# KeyBoard-RP2040_P2.net
KiCad netlist of a schematic drawn in Altium Designer
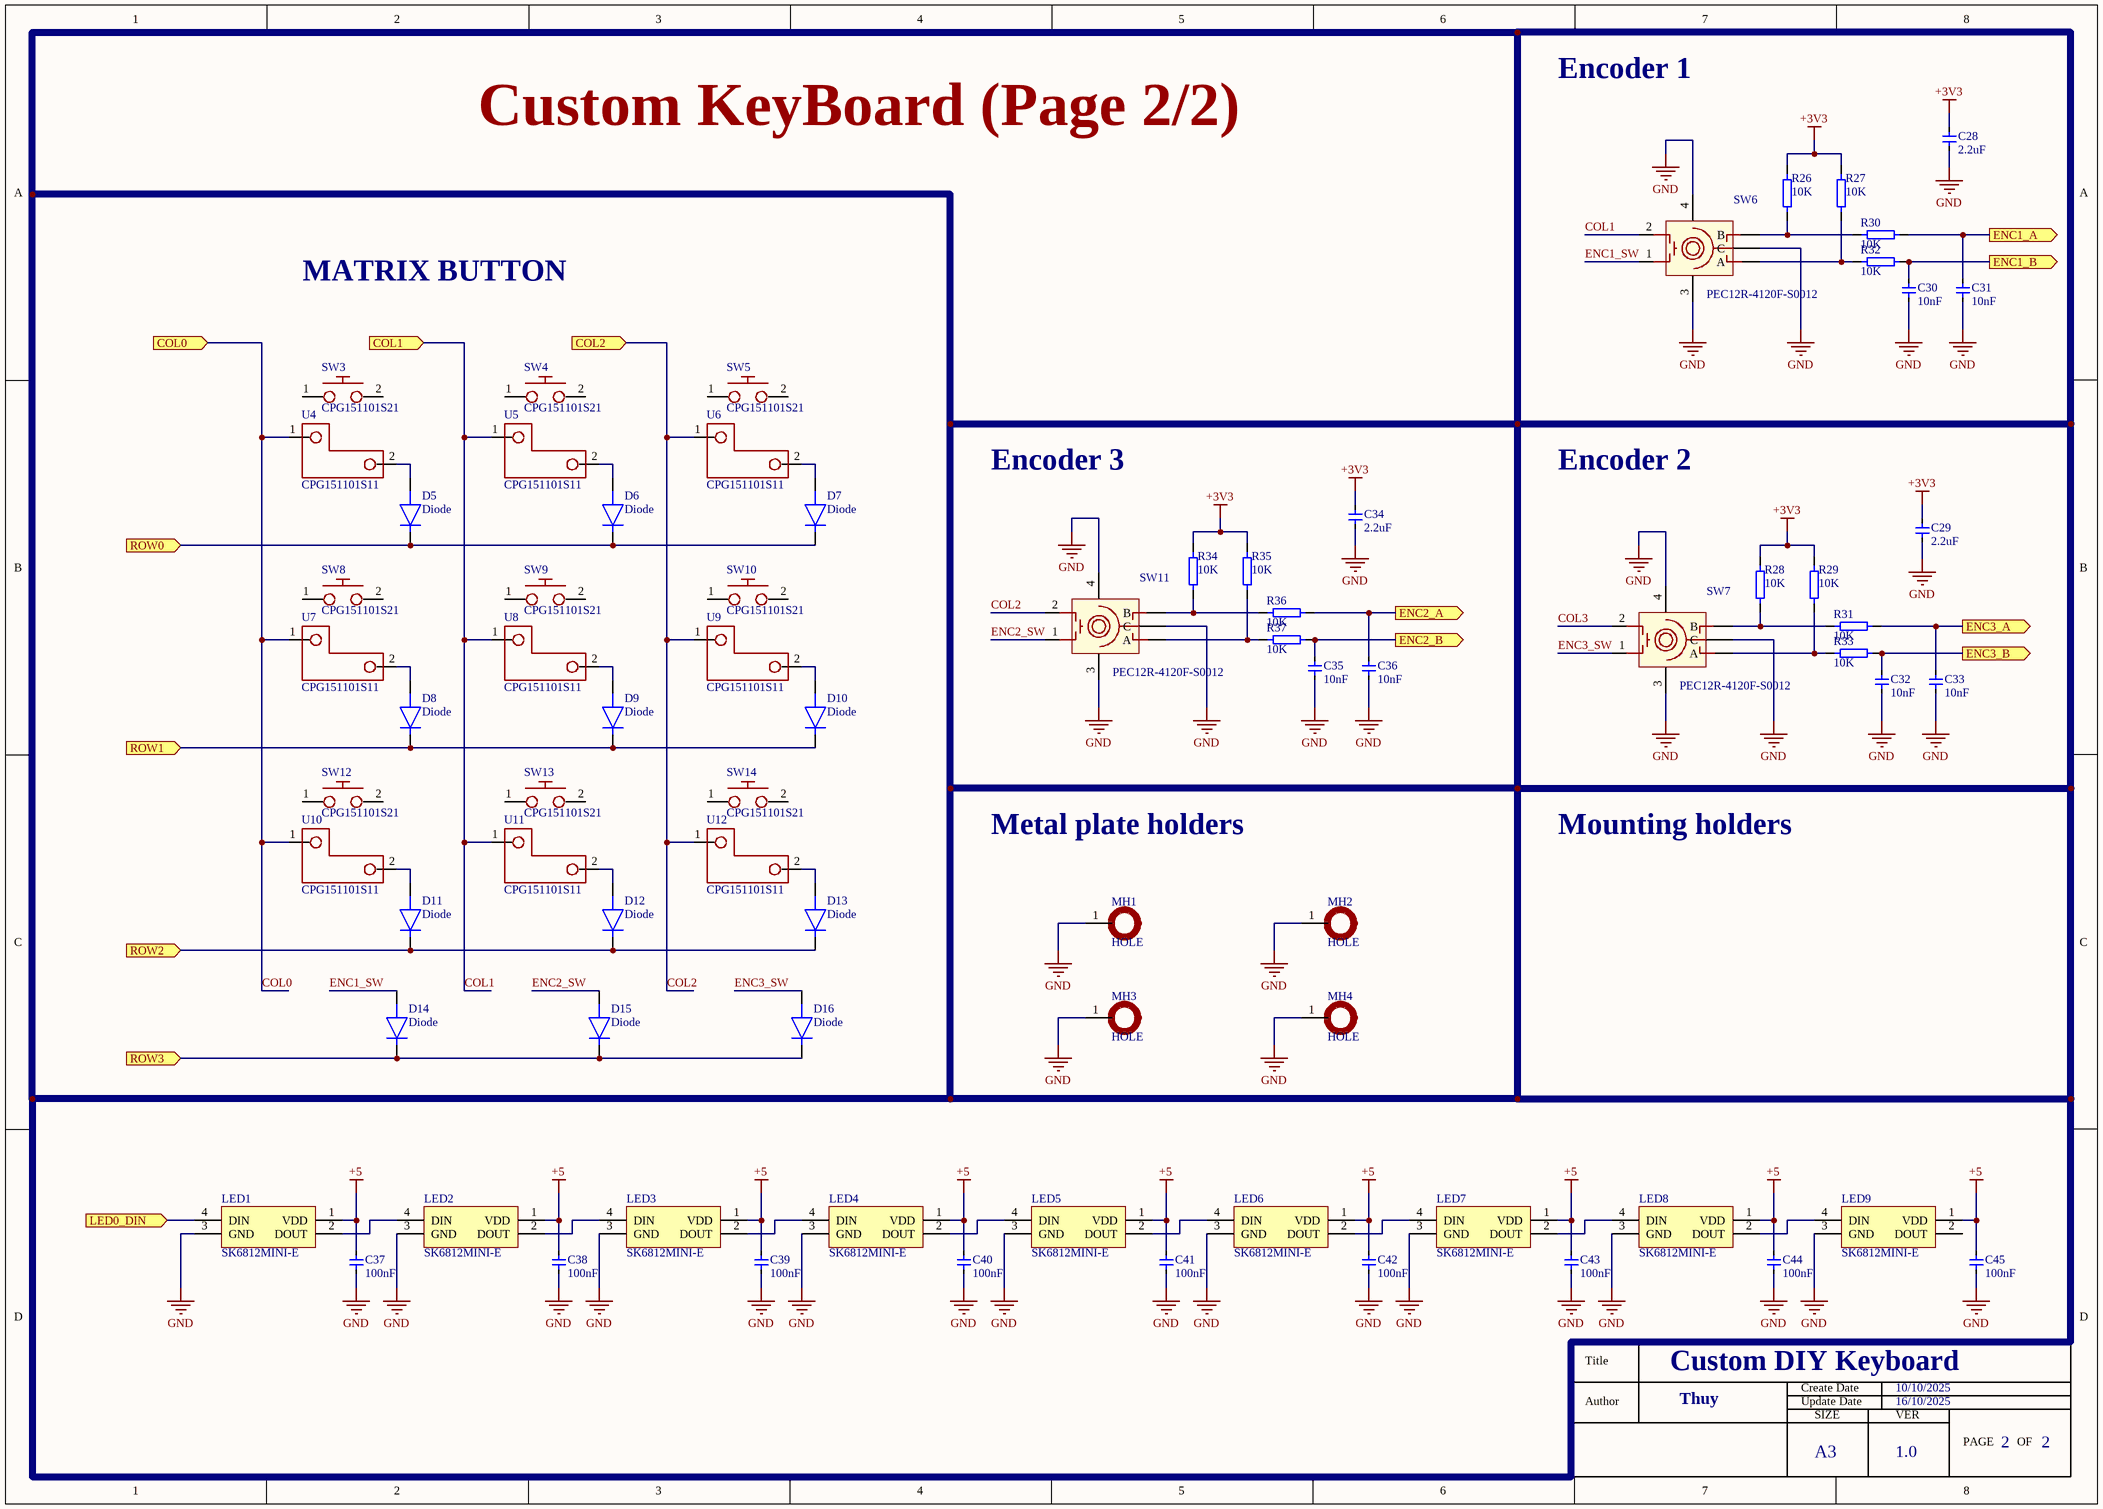
[diagram p0: KeyBoard-RP2040_P2.SchDoc]

(export (version "E")
  (design (tool "Eeschema 10.0.6"))
  (components
    (comp (ref "C28")
      (value "2.2uF")
      (footprint "C 0.79 0.54")
      (description "SMD")
      (libsource (lib "SCHLib") (part "CAP 2.2uF"))
    )
    (comp (ref "C29")
      (value "2.2uF")
      (footprint "C 0.79 0.54")
      (description "SMD")
      (libsource (lib "SCHLib") (part "CAP 2.2uF"))
    )
    (comp (ref "C30")
      (value "10nF")
      (footprint "SMD 0.79 0.54")
      (description "SMD")
      (libsource (lib "SCHLib") (part "CAP 10nF"))
    )
    (comp (ref "C31")
      (value "10nF")
      (footprint "SMD 0.79 0.54")
      (description "SMD")
      (libsource (lib "SCHLib") (part "CAP 10nF"))
    )
    (comp (ref "C32")
      (value "10nF")
      (footprint "SMD 0.79 0.54")
      (description "SMD")
      (libsource (lib "SCHLib") (part "CAP 10nF"))
    )
    (comp (ref "C33")
      (value "10nF")
      (footprint "SMD 0.79 0.54")
      (description "SMD")
      (libsource (lib "SCHLib") (part "CAP 10nF"))
    )
    (comp (ref "C34")
      (value "2.2uF")
      (footprint "C 0.79 0.54")
      (description "SMD")
      (libsource (lib "SCHLib") (part "CAP 2.2uF"))
    )
    (comp (ref "C35")
      (value "10nF")
      (footprint "SMD 0.79 0.54")
      (description "SMD")
      (libsource (lib "SCHLib") (part "CAP 10nF"))
    )
    (comp (ref "C36")
      (value "10nF")
      (footprint "SMD 0.79 0.54")
      (description "SMD")
      (libsource (lib "SCHLib") (part "CAP 10nF"))
    )
    (comp (ref "C37")
      (value "100nF")
      (footprint "C 0.79 0.54")
      (description "SMD")
      (libsource (lib "SCHLib") (part "CAP 100nF"))
    )
    (comp (ref "C38")
      (value "100nF")
      (footprint "C 0.79 0.54")
      (description "SMD")
      (libsource (lib "SCHLib") (part "CAP 100nF"))
    )
    (comp (ref "C39")
      (value "100nF")
      (footprint "C 0.79 0.54")
      (description "SMD")
      (libsource (lib "SCHLib") (part "CAP 100nF"))
    )
    (comp (ref "C40")
      (value "100nF")
      (footprint "C 0.79 0.54")
      (description "SMD")
      (libsource (lib "SCHLib") (part "CAP 100nF"))
    )
    (comp (ref "C41")
      (value "100nF")
      (footprint "C 0.79 0.54")
      (description "SMD")
      (libsource (lib "SCHLib") (part "CAP 100nF"))
    )
    (comp (ref "C42")
      (value "100nF")
      (footprint "C 0.79 0.54")
      (description "SMD")
      (libsource (lib "SCHLib") (part "CAP 100nF"))
    )
    (comp (ref "C43")
      (value "100nF")
      (footprint "C 0.79 0.54")
      (description "SMD")
      (libsource (lib "SCHLib") (part "CAP 100nF"))
    )
    (comp (ref "C44")
      (value "100nF")
      (footprint "C 0.79 0.54")
      (description "SMD")
      (libsource (lib "SCHLib") (part "CAP 100nF"))
    )
    (comp (ref "C45")
      (value "100nF")
      (footprint "C 0.79 0.54")
      (description "SMD")
      (libsource (lib "SCHLib") (part "CAP 100nF"))
    )
    (comp (ref "D5")
      (value "Diode")
      (footprint "Diode")
      (description "SMD")
      (libsource (lib "SCHLib") (part "Diode"))
    )
    (comp (ref "D6")
      (value "Diode")
      (footprint "Diode")
      (description "SMD")
      (libsource (lib "SCHLib") (part "Diode"))
    )
    (comp (ref "D7")
      (value "Diode")
      (footprint "Diode")
      (description "SMD")
      (libsource (lib "SCHLib") (part "Diode"))
    )
    (comp (ref "D8")
      (value "Diode")
      (footprint "Diode")
      (description "SMD")
      (libsource (lib "SCHLib") (part "Diode"))
    )
    (comp (ref "D9")
      (value "Diode")
      (footprint "Diode")
      (description "SMD")
      (libsource (lib "SCHLib") (part "Diode"))
    )
    (comp (ref "D10")
      (value "Diode")
      (footprint "Diode")
      (description "SMD")
      (libsource (lib "SCHLib") (part "Diode"))
    )
    (comp (ref "D11")
      (value "Diode")
      (footprint "Diode")
      (description "SMD")
      (libsource (lib "SCHLib") (part "Diode"))
    )
    (comp (ref "D12")
      (value "Diode")
      (footprint "Diode")
      (description "SMD")
      (libsource (lib "SCHLib") (part "Diode"))
    )
    (comp (ref "D13")
      (value "Diode")
      (footprint "Diode")
      (description "SMD")
      (libsource (lib "SCHLib") (part "Diode"))
    )
    (comp (ref "D14")
      (value "Diode")
      (footprint "Diode")
      (description "SMD")
      (libsource (lib "SCHLib") (part "Diode"))
    )
    (comp (ref "D15")
      (value "Diode")
      (footprint "Diode")
      (description "SMD")
      (libsource (lib "SCHLib") (part "Diode"))
    )
    (comp (ref "D16")
      (value "Diode")
      (footprint "Diode")
      (description "SMD")
      (libsource (lib "SCHLib") (part "Diode"))
    )
    (comp (ref "LED1")
      (value "SK6812MINI-E")
      (footprint "LED-SK6812MINI-E")
      (description "RGB 3.7V~5.5V 0.6mA")
      (libsource (lib "SCHLib") (part "LED-SK6812MINI-E"))
    )
    (comp (ref "LED2")
      (value "SK6812MINI-E")
      (footprint "LED-SK6812MINI-E")
      (description "RGB 3.7V~5.5V 0.6mA")
      (libsource (lib "SCHLib") (part "LED-SK6812MINI-E"))
    )
    (comp (ref "LED3")
      (value "SK6812MINI-E")
      (footprint "LED-SK6812MINI-E")
      (description "RGB 3.7V~5.5V 0.6mA")
      (libsource (lib "SCHLib") (part "LED-SK6812MINI-E"))
    )
    (comp (ref "LED4")
      (value "SK6812MINI-E")
      (footprint "LED-SK6812MINI-E")
      (description "RGB 3.7V~5.5V 0.6mA")
      (libsource (lib "SCHLib") (part "LED-SK6812MINI-E"))
    )
    (comp (ref "LED5")
      (value "SK6812MINI-E")
      (footprint "LED-SK6812MINI-E")
      (description "RGB 3.7V~5.5V 0.6mA")
      (libsource (lib "SCHLib") (part "LED-SK6812MINI-E"))
    )
    (comp (ref "LED6")
      (value "SK6812MINI-E")
      (footprint "LED-SK6812MINI-E")
      (description "RGB 3.7V~5.5V 0.6mA")
      (libsource (lib "SCHLib") (part "LED-SK6812MINI-E"))
    )
    (comp (ref "LED7")
      (value "SK6812MINI-E")
      (footprint "LED-SK6812MINI-E")
      (description "RGB 3.7V~5.5V 0.6mA")
      (libsource (lib "SCHLib") (part "LED-SK6812MINI-E"))
    )
    (comp (ref "LED8")
      (value "SK6812MINI-E")
      (footprint "LED-SK6812MINI-E")
      (description "RGB 3.7V~5.5V 0.6mA")
      (libsource (lib "SCHLib") (part "LED-SK6812MINI-E"))
    )
    (comp (ref "LED9")
      (value "SK6812MINI-E")
      (footprint "LED-SK6812MINI-E")
      (description "RGB 3.7V~5.5V 0.6mA")
      (libsource (lib "SCHLib") (part "LED-SK6812MINI-E"))
    )
    (comp (ref "MH1") (value "HOLE") (footprint "Hole") (libsource (lib "SCHLib") (part "HOLE")))
    (comp (ref "MH2") (value "HOLE") (footprint "Hole") (libsource (lib "SCHLib") (part "HOLE")))
    (comp (ref "MH3") (value "HOLE") (footprint "Hole") (libsource (lib "SCHLib") (part "HOLE")))
    (comp (ref "MH4") (value "HOLE") (footprint "Hole") (libsource (lib "SCHLib") (part "HOLE")))
    (comp (ref "R26")
      (value "10K")
      (footprint "SMD 0.566 0.54")
      (description "SMD")
      (libsource (lib "SCHLib") (part "RES 10K"))
    )
    (comp (ref "R27")
      (value "10K")
      (footprint "SMD 0.566 0.54")
      (description "SMD")
      (libsource (lib "SCHLib") (part "RES 10K"))
    )
    (comp (ref "R28")
      (value "10K")
      (footprint "SMD 0.566 0.54")
      (description "SMD")
      (libsource (lib "SCHLib") (part "RES 10K"))
    )
    (comp (ref "R29")
      (value "10K")
      (footprint "SMD 0.566 0.54")
      (description "SMD")
      (libsource (lib "SCHLib") (part "RES 10K"))
    )
    (comp (ref "R30")
      (value "10K")
      (footprint "SMD 0.566 0.54")
      (description "SMD")
      (libsource (lib "") (part "RES 10K_1"))
    )
    (comp (ref "R31")
      (value "10K")
      (footprint "SMD 0.566 0.54")
      (description "SMD")
      (libsource (lib "") (part "RES 10K_1"))
    )
    (comp (ref "R32")
      (value "10K")
      (footprint "SMD 0.566 0.54")
      (description "SMD")
      (libsource (lib "") (part "RES 10K_1"))
    )
    (comp (ref "R33")
      (value "10K")
      (footprint "SMD 0.566 0.54")
      (description "SMD")
      (libsource (lib "") (part "RES 10K_1"))
    )
    (comp (ref "R34")
      (value "10K")
      (footprint "SMD 0.566 0.54")
      (description "SMD")
      (libsource (lib "SCHLib") (part "RES 10K"))
    )
    (comp (ref "R35")
      (value "10K")
      (footprint "SMD 0.566 0.54")
      (description "SMD")
      (libsource (lib "SCHLib") (part "RES 10K"))
    )
    (comp (ref "R36")
      (value "10K")
      (footprint "SMD 0.566 0.54")
      (description "SMD")
      (libsource (lib "") (part "RES 10K_1"))
    )
    (comp (ref "R37")
      (value "10K")
      (footprint "SMD 0.566 0.54")
      (description "SMD")
      (libsource (lib "") (part "RES 10K_1"))
    )
    (comp (ref "SW3")
      (value "CPG151101S21")
      (footprint "CPG151101S21")
      (libsource (lib "SCHLib") (part "SW-CPG151101S21"))
    )
    (comp (ref "SW4")
      (value "CPG151101S21")
      (footprint "CPG151101S21")
      (libsource (lib "SCHLib") (part "SW-CPG151101S21"))
    )
    (comp (ref "SW5")
      (value "CPG151101S21")
      (footprint "CPG151101S21")
      (libsource (lib "SCHLib") (part "SW-CPG151101S21"))
    )
    (comp (ref "SW6")
      (value "PEC12R-4120F-S0012")
      (footprint "SW-encoder")
      (libsource (lib "SCHLib") (part "Encoder-PEC12R"))
    )
    (comp (ref "SW7")
      (value "PEC12R-4120F-S0012")
      (footprint "SW-encoder")
      (libsource (lib "SCHLib") (part "Encoder-PEC12R"))
    )
    (comp (ref "SW8")
      (value "CPG151101S21")
      (footprint "CPG151101S21")
      (libsource (lib "SCHLib") (part "SW-CPG151101S21"))
    )
    (comp (ref "SW9")
      (value "CPG151101S21")
      (footprint "CPG151101S21")
      (libsource (lib "SCHLib") (part "SW-CPG151101S21"))
    )
    (comp (ref "SW10")
      (value "CPG151101S21")
      (footprint "CPG151101S21")
      (libsource (lib "SCHLib") (part "SW-CPG151101S21"))
    )
    (comp (ref "SW11")
      (value "PEC12R-4120F-S0012")
      (footprint "SW-encoder")
      (libsource (lib "SCHLib") (part "Encoder-PEC12R"))
    )
    (comp (ref "SW12")
      (value "CPG151101S21")
      (footprint "CPG151101S21")
      (libsource (lib "SCHLib") (part "SW-CPG151101S21"))
    )
    (comp (ref "SW13")
      (value "CPG151101S21")
      (footprint "CPG151101S21")
      (libsource (lib "SCHLib") (part "SW-CPG151101S21"))
    )
    (comp (ref "SW14")
      (value "CPG151101S21")
      (footprint "CPG151101S21")
      (libsource (lib "SCHLib") (part "SW-CPG151101S21"))
    )
    (comp (ref "U4")
      (value "CPG151101S11")
      (footprint "CPG151101S11")
      (libsource (lib "SCHLib") (part "SW-CPG151101S11"))
    )
    (comp (ref "U5")
      (value "CPG151101S11")
      (footprint "CPG151101S11")
      (libsource (lib "SCHLib") (part "SW-CPG151101S11"))
    )
    (comp (ref "U6")
      (value "CPG151101S11")
      (footprint "CPG151101S11")
      (libsource (lib "SCHLib") (part "SW-CPG151101S11"))
    )
    (comp (ref "U7")
      (value "CPG151101S11")
      (footprint "CPG151101S11")
      (libsource (lib "SCHLib") (part "SW-CPG151101S11"))
    )
    (comp (ref "U8")
      (value "CPG151101S11")
      (footprint "CPG151101S11")
      (libsource (lib "SCHLib") (part "SW-CPG151101S11"))
    )
    (comp (ref "U9")
      (value "CPG151101S11")
      (footprint "CPG151101S11")
      (libsource (lib "SCHLib") (part "SW-CPG151101S11"))
    )
    (comp (ref "U10")
      (value "CPG151101S11")
      (footprint "CPG151101S11")
      (libsource (lib "SCHLib") (part "SW-CPG151101S11"))
    )
    (comp (ref "U11")
      (value "CPG151101S11")
      (footprint "CPG151101S11")
      (libsource (lib "SCHLib") (part "SW-CPG151101S11"))
    )
    (comp (ref "U12")
      (value "CPG151101S11")
      (footprint "CPG151101S11")
      (libsource (lib "SCHLib") (part "SW-CPG151101S11"))
    )
  )
  (nets
    (net (code "1") (name "+3V3") (class "Default")
      (node (ref "C28") (pin "2") (pinfunction "2_2") (pintype "passive"))
      (node (ref "C29") (pin "2") (pinfunction "2_2") (pintype "passive"))
      (node (ref "C34") (pin "2") (pinfunction "2_2") (pintype "passive"))
      (node (ref "R26") (pin "2") (pinfunction "2_2") (pintype "passive"))
      (node (ref "R27") (pin "2") (pinfunction "2_2") (pintype "passive"))
      (node (ref "R28") (pin "2") (pinfunction "2_2") (pintype "passive"))
      (node (ref "R29") (pin "2") (pinfunction "2_2") (pintype "passive"))
      (node (ref "R34") (pin "2") (pinfunction "2_2") (pintype "passive"))
      (node (ref "R35") (pin "2") (pinfunction "2_2") (pintype "passive"))
    )
    (net (code "2") (name "+5") (class "Default")
      (node (ref "C37") (pin "2") (pinfunction "2_2") (pintype "passive"))
      (node (ref "C38") (pin "2") (pinfunction "2_2") (pintype "passive"))
      (node (ref "C39") (pin "2") (pinfunction "2_2") (pintype "passive"))
      (node (ref "C40") (pin "2") (pinfunction "2_2") (pintype "passive"))
      (node (ref "C41") (pin "2") (pinfunction "2_2") (pintype "passive"))
      (node (ref "C42") (pin "2") (pinfunction "2_2") (pintype "passive"))
      (node (ref "C43") (pin "2") (pinfunction "2_2") (pintype "passive"))
      (node (ref "C44") (pin "2") (pinfunction "2_2") (pintype "passive"))
      (node (ref "C45") (pin "2") (pinfunction "2_2") (pintype "passive"))
      (node (ref "LED1") (pin "1") (pinfunction "VDD_1") (pintype "passive"))
      (node (ref "LED2") (pin "1") (pinfunction "VDD_1") (pintype "passive"))
      (node (ref "LED3") (pin "1") (pinfunction "VDD_1") (pintype "passive"))
      (node (ref "LED4") (pin "1") (pinfunction "VDD_1") (pintype "passive"))
      (node (ref "LED5") (pin "1") (pinfunction "VDD_1") (pintype "passive"))
      (node (ref "LED6") (pin "1") (pinfunction "VDD_1") (pintype "passive"))
      (node (ref "LED7") (pin "1") (pinfunction "VDD_1") (pintype "passive"))
      (node (ref "LED8") (pin "1") (pinfunction "VDD_1") (pintype "passive"))
      (node (ref "LED9") (pin "1") (pinfunction "VDD_1") (pintype "passive"))
    )
    (net (code "3") (name "/COL0") (class "Default")
      (node (ref "U10") (pin "1") (pinfunction "1_1") (pintype "passive"))
      (node (ref "U4") (pin "1") (pinfunction "1_1") (pintype "passive"))
      (node (ref "U7") (pin "1") (pinfunction "1_1") (pintype "passive"))
    )
    (net (code "4") (name "/COL1") (class "Default")
      (node (ref "SW6") (pin "2") (pinfunction "2_2") (pintype "passive"))
      (node (ref "U11") (pin "1") (pinfunction "1_1") (pintype "passive"))
      (node (ref "U5") (pin "1") (pinfunction "1_1") (pintype "passive"))
      (node (ref "U8") (pin "1") (pinfunction "1_1") (pintype "passive"))
    )
    (net (code "5") (name "/COL2") (class "Default")
      (node (ref "SW11") (pin "2") (pinfunction "2_2") (pintype "passive"))
      (node (ref "U12") (pin "1") (pinfunction "1_1") (pintype "passive"))
      (node (ref "U6") (pin "1") (pinfunction "1_1") (pintype "passive"))
      (node (ref "U9") (pin "1") (pinfunction "1_1") (pintype "passive"))
    )
    (net (code "6") (name "/COL3") (class "Default")
      (node (ref "SW7") (pin "2") (pinfunction "2_2") (pintype "passive"))
    )
    (net (code "7") (name "/ENC1_A") (class "Default")
      (node (ref "C31") (pin "2") (pinfunction "2_2") (pintype "passive"))
      (node (ref "R30") (pin "1") (pinfunction "1_1") (pintype "passive"))
    )
    (net (code "8") (name "/ENC1_B") (class "Default")
      (node (ref "C30") (pin "2") (pinfunction "2_2") (pintype "passive"))
      (node (ref "R32") (pin "1") (pinfunction "1_1") (pintype "passive"))
    )
    (net (code "9") (name "/ENC1_SW") (class "Default")
      (node (ref "D14") (pin "2") (pinfunction "2_2") (pintype "passive"))
      (node (ref "SW6") (pin "1") (pinfunction "1_1") (pintype "passive"))
    )
    (net (code "10") (name "/ENC2_A") (class "Default")
      (node (ref "C36") (pin "2") (pinfunction "2_2") (pintype "passive"))
      (node (ref "R36") (pin "1") (pinfunction "1_1") (pintype "passive"))
    )
    (net (code "11") (name "/ENC2_B") (class "Default")
      (node (ref "C35") (pin "2") (pinfunction "2_2") (pintype "passive"))
      (node (ref "R37") (pin "1") (pinfunction "1_1") (pintype "passive"))
    )
    (net (code "12") (name "/ENC2_SW") (class "Default")
      (node (ref "D15") (pin "2") (pinfunction "2_2") (pintype "passive"))
      (node (ref "SW11") (pin "1") (pinfunction "1_1") (pintype "passive"))
    )
    (net (code "13") (name "/ENC3_A") (class "Default")
      (node (ref "C33") (pin "2") (pinfunction "2_2") (pintype "passive"))
      (node (ref "R31") (pin "1") (pinfunction "1_1") (pintype "passive"))
    )
    (net (code "14") (name "/ENC3_B") (class "Default")
      (node (ref "C32") (pin "2") (pinfunction "2_2") (pintype "passive"))
      (node (ref "R33") (pin "1") (pinfunction "1_1") (pintype "passive"))
    )
    (net (code "15") (name "/ENC3_SW") (class "Default")
      (node (ref "D16") (pin "2") (pinfunction "2_2") (pintype "passive"))
      (node (ref "SW7") (pin "1") (pinfunction "1_1") (pintype "passive"))
    )
    (net (code "16") (name "/LED0_DIN") (class "Default")
      (node (ref "LED1") (pin "4") (pinfunction "DIN_4") (pintype "passive"))
    )
    (net (code "17") (name "/ROW0") (class "Default")
      (node (ref "D5") (pin "1") (pinfunction "1_1") (pintype "passive"))
      (node (ref "D6") (pin "1") (pinfunction "1_1") (pintype "passive"))
      (node (ref "D7") (pin "1") (pinfunction "1_1") (pintype "passive"))
    )
    (net (code "18") (name "/ROW1") (class "Default")
      (node (ref "D10") (pin "1") (pinfunction "1_1") (pintype "passive"))
      (node (ref "D8") (pin "1") (pinfunction "1_1") (pintype "passive"))
      (node (ref "D9") (pin "1") (pinfunction "1_1") (pintype "passive"))
    )
    (net (code "19") (name "/ROW2") (class "Default")
      (node (ref "D11") (pin "1") (pinfunction "1_1") (pintype "passive"))
      (node (ref "D12") (pin "1") (pinfunction "1_1") (pintype "passive"))
      (node (ref "D13") (pin "1") (pinfunction "1_1") (pintype "passive"))
    )
    (net (code "20") (name "/ROW3") (class "Default")
      (node (ref "D14") (pin "1") (pinfunction "1_1") (pintype "passive"))
      (node (ref "D15") (pin "1") (pinfunction "1_1") (pintype "passive"))
      (node (ref "D16") (pin "1") (pinfunction "1_1") (pintype "passive"))
    )
    (net (code "21") (name "GND") (class "Default")
      (node (ref "C28") (pin "1") (pinfunction "1_1") (pintype "passive"))
      (node (ref "C29") (pin "1") (pinfunction "1_1") (pintype "passive"))
      (node (ref "C30") (pin "1") (pinfunction "1_1") (pintype "passive"))
      (node (ref "C31") (pin "1") (pinfunction "1_1") (pintype "passive"))
      (node (ref "C32") (pin "1") (pinfunction "1_1") (pintype "passive"))
      (node (ref "C33") (pin "1") (pinfunction "1_1") (pintype "passive"))
      (node (ref "C34") (pin "1") (pinfunction "1_1") (pintype "passive"))
      (node (ref "C35") (pin "1") (pinfunction "1_1") (pintype "passive"))
      (node (ref "C36") (pin "1") (pinfunction "1_1") (pintype "passive"))
      (node (ref "C37") (pin "1") (pinfunction "1_1") (pintype "passive"))
      (node (ref "C38") (pin "1") (pinfunction "1_1") (pintype "passive"))
      (node (ref "C39") (pin "1") (pinfunction "1_1") (pintype "passive"))
      (node (ref "C40") (pin "1") (pinfunction "1_1") (pintype "passive"))
      (node (ref "C41") (pin "1") (pinfunction "1_1") (pintype "passive"))
      (node (ref "C42") (pin "1") (pinfunction "1_1") (pintype "passive"))
      (node (ref "C43") (pin "1") (pinfunction "1_1") (pintype "passive"))
      (node (ref "C44") (pin "1") (pinfunction "1_1") (pintype "passive"))
      (node (ref "C45") (pin "1") (pinfunction "1_1") (pintype "passive"))
      (node (ref "LED1") (pin "3") (pinfunction "GND_3") (pintype "passive"))
      (node (ref "LED2") (pin "3") (pinfunction "GND_3") (pintype "passive"))
      (node (ref "LED3") (pin "3") (pinfunction "GND_3") (pintype "passive"))
      (node (ref "LED4") (pin "3") (pinfunction "GND_3") (pintype "passive"))
      (node (ref "LED5") (pin "3") (pinfunction "GND_3") (pintype "passive"))
      (node (ref "LED6") (pin "3") (pinfunction "GND_3") (pintype "passive"))
      (node (ref "LED7") (pin "3") (pinfunction "GND_3") (pintype "passive"))
      (node (ref "LED8") (pin "3") (pinfunction "GND_3") (pintype "passive"))
      (node (ref "LED9") (pin "3") (pinfunction "GND_3") (pintype "passive"))
      (node (ref "MH1") (pin "1") (pinfunction "1_1") (pintype "passive"))
      (node (ref "MH2") (pin "1") (pinfunction "1_1") (pintype "passive"))
      (node (ref "MH3") (pin "1") (pinfunction "1_1") (pintype "passive"))
      (node (ref "MH4") (pin "1") (pinfunction "1_1") (pintype "passive"))
      (node (ref "SW11") (pin "3") (pinfunction "3_3") (pintype "passive"))
      (node (ref "SW11") (pin "4") (pinfunction "4_4") (pintype "passive"))
      (node (ref "SW11") (pin "6") (pinfunction "C_6") (pintype "passive"))
      (node (ref "SW6") (pin "3") (pinfunction "3_3") (pintype "passive"))
      (node (ref "SW6") (pin "4") (pinfunction "4_4") (pintype "passive"))
      (node (ref "SW6") (pin "6") (pinfunction "C_6") (pintype "passive"))
      (node (ref "SW7") (pin "3") (pinfunction "3_3") (pintype "passive"))
      (node (ref "SW7") (pin "4") (pinfunction "4_4") (pintype "passive"))
      (node (ref "SW7") (pin "6") (pinfunction "C_6") (pintype "passive"))
    )
    (net (code "22") (name "Net-(D5-Pad2)") (class "Default")
      (node (ref "D5") (pin "2") (pinfunction "2_2") (pintype "passive"))
      (node (ref "U4") (pin "2") (pinfunction "2_2") (pintype "passive"))
    )
    (net (code "23") (name "Net-(D6-Pad2)") (class "Default")
      (node (ref "D6") (pin "2") (pinfunction "2_2") (pintype "passive"))
      (node (ref "U5") (pin "2") (pinfunction "2_2") (pintype "passive"))
    )
    (net (code "24") (name "Net-(D7-Pad2)") (class "Default")
      (node (ref "D7") (pin "2") (pinfunction "2_2") (pintype "passive"))
      (node (ref "U6") (pin "2") (pinfunction "2_2") (pintype "passive"))
    )
    (net (code "25") (name "Net-(D8-Pad2)") (class "Default")
      (node (ref "D8") (pin "2") (pinfunction "2_2") (pintype "passive"))
      (node (ref "U7") (pin "2") (pinfunction "2_2") (pintype "passive"))
    )
    (net (code "26") (name "Net-(D9-Pad2)") (class "Default")
      (node (ref "D9") (pin "2") (pinfunction "2_2") (pintype "passive"))
      (node (ref "U8") (pin "2") (pinfunction "2_2") (pintype "passive"))
    )
    (net (code "27") (name "Net-(D10-Pad2)") (class "Default")
      (node (ref "D10") (pin "2") (pinfunction "2_2") (pintype "passive"))
      (node (ref "U9") (pin "2") (pinfunction "2_2") (pintype "passive"))
    )
    (net (code "28") (name "Net-(D11-Pad2)") (class "Default")
      (node (ref "D11") (pin "2") (pinfunction "2_2") (pintype "passive"))
      (node (ref "U10") (pin "2") (pinfunction "2_2") (pintype "passive"))
    )
    (net (code "29") (name "Net-(D12-Pad2)") (class "Default")
      (node (ref "D12") (pin "2") (pinfunction "2_2") (pintype "passive"))
      (node (ref "U11") (pin "2") (pinfunction "2_2") (pintype "passive"))
    )
    (net (code "30") (name "Net-(D13-Pad2)") (class "Default")
      (node (ref "D13") (pin "2") (pinfunction "2_2") (pintype "passive"))
      (node (ref "U12") (pin "2") (pinfunction "2_2") (pintype "passive"))
    )
    (net (code "31") (name "Net-(LED1-DOUT)") (class "Default")
      (node (ref "LED1") (pin "2") (pinfunction "DOUT_2") (pintype "passive"))
      (node (ref "LED2") (pin "4") (pinfunction "DIN_4") (pintype "passive"))
    )
    (net (code "32") (name "Net-(LED2-DOUT)") (class "Default")
      (node (ref "LED2") (pin "2") (pinfunction "DOUT_2") (pintype "passive"))
      (node (ref "LED3") (pin "4") (pinfunction "DIN_4") (pintype "passive"))
    )
    (net (code "33") (name "Net-(LED3-DOUT)") (class "Default")
      (node (ref "LED3") (pin "2") (pinfunction "DOUT_2") (pintype "passive"))
      (node (ref "LED4") (pin "4") (pinfunction "DIN_4") (pintype "passive"))
    )
    (net (code "34") (name "Net-(LED4-DOUT)") (class "Default")
      (node (ref "LED4") (pin "2") (pinfunction "DOUT_2") (pintype "passive"))
      (node (ref "LED5") (pin "4") (pinfunction "DIN_4") (pintype "passive"))
    )
    (net (code "35") (name "Net-(LED5-DOUT)") (class "Default")
      (node (ref "LED5") (pin "2") (pinfunction "DOUT_2") (pintype "passive"))
      (node (ref "LED6") (pin "4") (pinfunction "DIN_4") (pintype "passive"))
    )
    (net (code "36") (name "Net-(LED6-DOUT)") (class "Default")
      (node (ref "LED6") (pin "2") (pinfunction "DOUT_2") (pintype "passive"))
      (node (ref "LED7") (pin "4") (pinfunction "DIN_4") (pintype "passive"))
    )
    (net (code "37") (name "Net-(LED7-DOUT)") (class "Default")
      (node (ref "LED7") (pin "2") (pinfunction "DOUT_2") (pintype "passive"))
      (node (ref "LED8") (pin "4") (pinfunction "DIN_4") (pintype "passive"))
    )
    (net (code "38") (name "Net-(LED8-DOUT)") (class "Default")
      (node (ref "LED8") (pin "2") (pinfunction "DOUT_2") (pintype "passive"))
      (node (ref "LED9") (pin "4") (pinfunction "DIN_4") (pintype "passive"))
    )
    (net (code "39") (name "Net-(SW6-A)") (class "Default")
      (node (ref "R27") (pin "1") (pinfunction "1_1") (pintype "passive"))
      (node (ref "R32") (pin "2") (pinfunction "2_2") (pintype "passive"))
      (node (ref "SW6") (pin "5") (pinfunction "A_5") (pintype "passive"))
    )
    (net (code "40") (name "Net-(SW6-B)") (class "Default")
      (node (ref "R26") (pin "1") (pinfunction "1_1") (pintype "passive"))
      (node (ref "R30") (pin "2") (pinfunction "2_2") (pintype "passive"))
      (node (ref "SW6") (pin "7") (pinfunction "B_7") (pintype "passive"))
    )
    (net (code "41") (name "Net-(SW7-A)") (class "Default")
      (node (ref "R29") (pin "1") (pinfunction "1_1") (pintype "passive"))
      (node (ref "R33") (pin "2") (pinfunction "2_2") (pintype "passive"))
      (node (ref "SW7") (pin "5") (pinfunction "A_5") (pintype "passive"))
    )
    (net (code "42") (name "Net-(SW7-B)") (class "Default")
      (node (ref "R28") (pin "1") (pinfunction "1_1") (pintype "passive"))
      (node (ref "R31") (pin "2") (pinfunction "2_2") (pintype "passive"))
      (node (ref "SW7") (pin "7") (pinfunction "B_7") (pintype "passive"))
    )
    (net (code "43") (name "Net-(SW11-A)") (class "Default")
      (node (ref "R35") (pin "1") (pinfunction "1_1") (pintype "passive"))
      (node (ref "R37") (pin "2") (pinfunction "2_2") (pintype "passive"))
      (node (ref "SW11") (pin "5") (pinfunction "A_5") (pintype "passive"))
    )
    (net (code "44") (name "Net-(SW11-B)") (class "Default")
      (node (ref "R34") (pin "1") (pinfunction "1_1") (pintype "passive"))
      (node (ref "R36") (pin "2") (pinfunction "2_2") (pintype "passive"))
      (node (ref "SW11") (pin "7") (pinfunction "B_7") (pintype "passive"))
    )
    (net (code "45") (name "unconnected-(LED9-DOUT-Pad2)") (class "Default")
      (node (ref "LED9") (pin "2") (pinfunction "DOUT_2") (pintype "passive"))
    )
    (net (code "46") (name "unconnected-(SW3-Pad1)") (class "Default")
      (node (ref "SW3") (pin "1") (pinfunction "1_1") (pintype "passive"))
    )
    (net (code "47") (name "unconnected-(SW3-Pad2)") (class "Default")
      (node (ref "SW3") (pin "2") (pinfunction "2_2") (pintype "passive"))
    )
    (net (code "48") (name "unconnected-(SW4-Pad1)") (class "Default")
      (node (ref "SW4") (pin "1") (pinfunction "1_1") (pintype "passive"))
    )
    (net (code "49") (name "unconnected-(SW4-Pad2)") (class "Default")
      (node (ref "SW4") (pin "2") (pinfunction "2_2") (pintype "passive"))
    )
    (net (code "50") (name "unconnected-(SW5-Pad1)") (class "Default")
      (node (ref "SW5") (pin "1") (pinfunction "1_1") (pintype "passive"))
    )
    (net (code "51") (name "unconnected-(SW5-Pad2)") (class "Default")
      (node (ref "SW5") (pin "2") (pinfunction "2_2") (pintype "passive"))
    )
    (net (code "52") (name "unconnected-(SW8-Pad1)") (class "Default")
      (node (ref "SW8") (pin "1") (pinfunction "1_1") (pintype "passive"))
    )
    (net (code "53") (name "unconnected-(SW8-Pad2)") (class "Default")
      (node (ref "SW8") (pin "2") (pinfunction "2_2") (pintype "passive"))
    )
    (net (code "54") (name "unconnected-(SW9-Pad1)") (class "Default")
      (node (ref "SW9") (pin "1") (pinfunction "1_1") (pintype "passive"))
    )
    (net (code "55") (name "unconnected-(SW9-Pad2)") (class "Default")
      (node (ref "SW9") (pin "2") (pinfunction "2_2") (pintype "passive"))
    )
    (net (code "56") (name "unconnected-(SW10-Pad1)") (class "Default")
      (node (ref "SW10") (pin "1") (pinfunction "1_1") (pintype "passive"))
    )
    (net (code "57") (name "unconnected-(SW10-Pad2)") (class "Default")
      (node (ref "SW10") (pin "2") (pinfunction "2_2") (pintype "passive"))
    )
    (net (code "58") (name "unconnected-(SW12-Pad1)") (class "Default")
      (node (ref "SW12") (pin "1") (pinfunction "1_1") (pintype "passive"))
    )
    (net (code "59") (name "unconnected-(SW12-Pad2)") (class "Default")
      (node (ref "SW12") (pin "2") (pinfunction "2_2") (pintype "passive"))
    )
    (net (code "60") (name "unconnected-(SW13-Pad1)") (class "Default")
      (node (ref "SW13") (pin "1") (pinfunction "1_1") (pintype "passive"))
    )
    (net (code "61") (name "unconnected-(SW13-Pad2)") (class "Default")
      (node (ref "SW13") (pin "2") (pinfunction "2_2") (pintype "passive"))
    )
    (net (code "62") (name "unconnected-(SW14-Pad1)") (class "Default")
      (node (ref "SW14") (pin "1") (pinfunction "1_1") (pintype "passive"))
    )
    (net (code "63") (name "unconnected-(SW14-Pad2)") (class "Default")
      (node (ref "SW14") (pin "2") (pinfunction "2_2") (pintype "passive"))
    )
  )
)
